# 02_RF_FRONT_END.net
KiCad netlist of a schematic drawn in Altium Designer
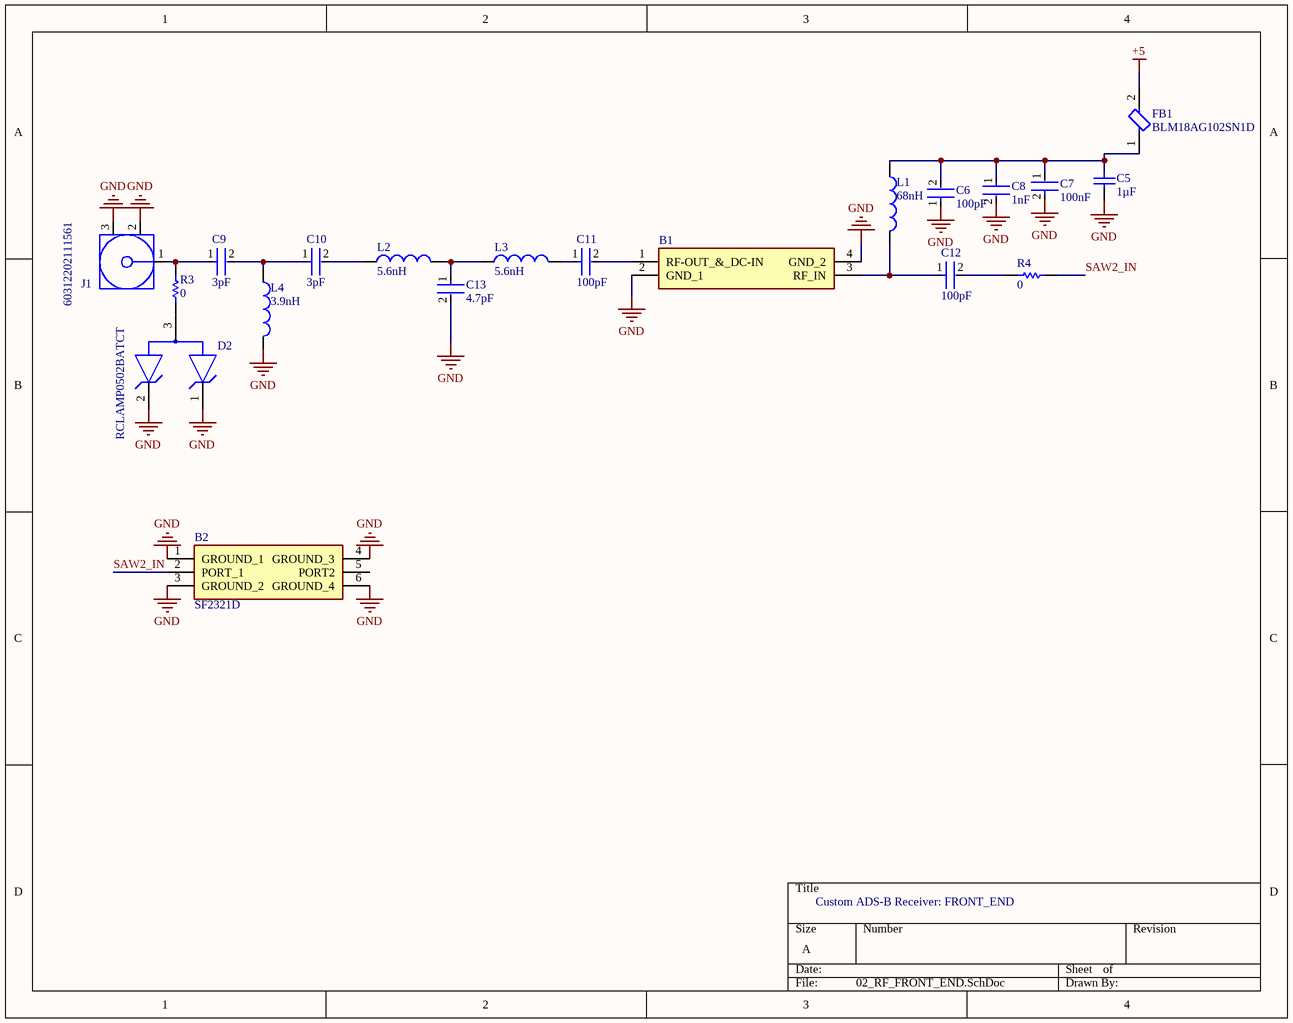
[diagram p0: 02_RF_FRONT_END.SchDoc]

(export (version "E")
  (design (tool "Eeschema 10.0.6"))
  (components
    (comp (ref "B1")
      (value "PSA4-5043+")
      (footprint "PSA45043")
      (libsource (lib "Maksym Pleshyvtsev") (part "PSA4-5043+"))
    )
    (comp (ref "B2")
      (value "SF2321D")
      (footprint "SF2321D")
      (description "Signal Conditioning 433.92MHZ")
      (fields (field (name "MOUSER PART NUMBER") "81-SF2321D"))
      (libsource (lib "Maksym Pleshyvtsev") (part "SF2321D"))
    )
    (comp (ref "C5")
      (value "1µF")
      (footprint "RESC1608X100N")
      (description "0603 1 uF 10 V ±10% Tolerance X5R SMT Multilayer Ceramic Capacitor")
      (fields (field (name "TOLERANCE") "10%") (field (name "Comment") "GRM188R61A105KA61D"))
      (libsource (lib "Maksym Pleshyvtsev") (part "CAP-NP-2"))
    )
    (comp (ref "C6")
      (value "100pF")
      (footprint "FP-GCM155-0_05-MFG")
      (description "50V 100pF C0G ±5% 0402 Multilayer Ceramic Capacitors MLCC - SMD/SMT ROHS")
      (fields (field (name "TOLERANCE") "5%") (field (name "Comment") "GCM1555C1H101JA16J"))
      (libsource (lib "Maksym Pleshyvtsev") (part "02cd4be3c70576c341d710602a673aa"))
    )
    (comp (ref "C7")
      (value "100nF")
      (footprint "FP-GRM15-MFG")
      (description "16V 100nF X7R ±10% 0402 Multilayer Ceramic Capacitors MLCC - SMD/SMT ROHS")
      (fields (field (name "TOLERANCE") "10%") (field (name "Comment") "GRM155R71C104KA88D"))
      (libsource (lib "Maksym Pleshyvtsev") (part "236180d848d6139a670b325ea6854c9"))
    )
    (comp (ref "C8")
      (value "1nF")
      (footprint "FP-GRM155-0_05-MFG")
      (description "50V 1nF C0G ±5% 0402 Multilayer Ceramic Capacitors MLCC - SMD/SMT ROHS")
      (fields (field (name "TOLERANCE") "5%") (field (name "Comment") "GRM1555C1H102JA01D"))
      (libsource (lib "Maksym Pleshyvtsev") (part "02cd4be3c70576c341d710602a673aa"))
    )
    (comp (ref "C9")
      (value "3pF")
      (footprint "FP-GJM155-0_05-IPC_A")
      (description "0402 3 pF 50V ±0.25 pF Tolerance C0G SMT Multilayer Ceramic Capacitor")
      (fields (field (name "Comment") "GJM1555C1H3R0CB01D"))
      (libsource (lib "Maksym Pleshyvtsev") (part "02cd4be3c70576c341d710602a673aa"))
    )
    (comp (ref "C10")
      (value "3pF")
      (footprint "FP-GJM155-0_05-IPC_A")
      (description "0402 3 pF 50V ±0.25 pF Tolerance C0G SMT Multilayer Ceramic Capacitor")
      (fields (field (name "Comment") "GJM1555C1H3R0CB01D"))
      (libsource (lib "Maksym Pleshyvtsev") (part "02cd4be3c70576c341d710602a673aa"))
    )
    (comp (ref "C11")
      (value "100pF")
      (footprint "FP-GCM155-0_05-MFG")
      (description "50V 100pF C0G ±5% 0402 Multilayer Ceramic Capacitors MLCC - SMD/SMT ROHS")
      (fields (field (name "TOLERANCE") "5%") (field (name "Comment") "GCM1555C1H101JA16J"))
      (libsource (lib "Maksym Pleshyvtsev") (part "02cd4be3c70576c341d710602a673aa"))
    )
    (comp (ref "C12")
      (value "100pF")
      (footprint "FP-GCM155-0_05-MFG")
      (description "50V 100pF C0G ±5% 0402 Multilayer Ceramic Capacitors MLCC - SMD/SMT ROHS")
      (fields (field (name "TOLERANCE") "5%") (field (name "Comment") "GCM1555C1H101JA16J"))
      (libsource (lib "Maksym Pleshyvtsev") (part "02cd4be3c70576c341d710602a673aa"))
    )
    (comp (ref "C13")
      (value "4.7pF")
      (footprint "FP-GJM155-0_05-MFG")
      (description "0402 4.7pF 50V ±0.25 pF Tolerance C0G SMT Multilayer Ceramic Capacitor")
      (fields (field (name "Comment") "GJM1555C1H4R7CB01D"))
      (libsource (lib "Maksym Pleshyvtsev") (part "02cd4be3c70576c341d710602a673aa"))
    )
    (comp (ref "D2")
      (value "RCLAMP0502BATCT")
      (footprint "FP-SC75-IPC_A")
      (description "ESD Suppressor Diode TVS Uni-Dir/Bi-Dir 5V 3-Pin SOT-523 T/R / TVS DIODE 5VWM 25VC SC75")
      (libsource (lib "Maksym Pleshyvtsev") (part "9603becf907846612ba46a8964e2875"))
    )
    (comp (ref "FB1")
      (value "BLM18AG102SN1D")
      (footprint "FP-BLM18-0_15-t0_8-MFG")
      (description "Ferrite Beads Multi-Layer 1KOhm 25% 100MHz 400mA 500mOhm DCR 0603 T/R")
      (libsource (lib "Maksym Pleshyvtsev") (part "5f30dd21d616792df468990f7003faa"))
    )
    (comp (ref "J1")
      (value "60312202111561")
      (footprint "60312202111561")
      (description "Rf Conn, Sma, Jack, 50 Ohm, End Launch Rohs Compliant: Yes")
      (libsource (lib "Maksym Pleshyvtsev") (part "Jack_2GND"))
    )
    (comp (ref "L1")
      (value "68nH")
      (footprint "INDC1811X102N")
      (description "RF inductor, ceramic core, 2% tol, SMT, RoHS, halogen-free")
      (fields (field (name "Comment") "Coilcraft 0603CS-68NX"))
      (libsource (lib "Maksym Pleshyvtsev") (part "IND-2"))
    )
    (comp (ref "L2")
      (value "5.6nH")
      (footprint "INDC1811X100N")
      (description "General Purpose Inductor, 0.0056uH, 5%, 1 Element, Ceramic-Core, SMD, 0603")
      (fields (field (name "TOLERANCE") "5%") (field (name "Comment") "0603CS5N6XJRW"))
      (libsource (lib "Maksym Pleshyvtsev") (part "IND-2"))
    )
    (comp (ref "L3")
      (value "5.6nH")
      (footprint "INDC1811X102N")
      (description "General Purpose Inductor, 0.0056uH, 5%, 1 Element, Ceramic-Core, SMD, 0603")
      (fields (field (name "TOLERANCE") "5%") (field (name "Comment") "0603CS5N6XJRW"))
      (libsource (lib "Maksym Pleshyvtsev") (part "IND-2"))
    )
    (comp (ref "L4")
      (value "3.9nH")
      (footprint "INDC1811X100N")
      (description "General Purpose Inductor, 0.0039uH, 5%, 1 Element, Ceramic-Core, SMD, 0603")
      (fields (field (name "TOLERANCE") "5%") (field (name "Comment") "0603CS-3N9XJRW"))
      (libsource (lib "Maksym Pleshyvtsev") (part "IND-2"))
    )
    (comp (ref "R3")
      (value "0")
      (footprint "RESC1608X55X25ML10T15")
      (description "Chip Resistor, 0 Ohm, 0.1 W, -55 to 155 degC, 0603 (1608 Metric)")
      (fields (field (name "POWER") "100mW") (field (name "TOLERANCE") "5%"))
      (libsource (lib "Maksym Pleshyvtsev") (part "RES-2"))
    )
    (comp (ref "R4")
      (value "0")
      (footprint "RESC1608X55X25ML10T15")
      (description "Chip Resistor, 0 Ohm, 0.1 W, -55 to 155 degC, 0603 (1608 Metric)")
      (fields (field (name "POWER") "100mW") (field (name "TOLERANCE") "5%"))
      (libsource (lib "Maksym Pleshyvtsev") (part "RES-2"))
    )
  )
  (nets
    (net (code "1") (name "+5") (class "Default")
      (node (ref "FB1") (pin "2") (pinfunction "2_2") (pintype "passive"))
    )
    (net (code "2") (name "/SAW2_IN") (class "Default")
      (node (ref "B2") (pin "2") (pinfunction "PORT_1_2") (pintype "passive"))
      (node (ref "R4") (pin "1") (pinfunction "1_1") (pintype "passive"))
    )
    (net (code "3") (name "GND") (class "Default")
      (node (ref "B1") (pin "2") (pinfunction "GND_1_2") (pintype "passive"))
      (node (ref "B1") (pin "4") (pinfunction "GND_2_4") (pintype "passive"))
      (node (ref "B2") (pin "1") (pinfunction "GROUND_1_1") (pintype "passive"))
      (node (ref "B2") (pin "3") (pinfunction "GROUND_2_3") (pintype "passive"))
      (node (ref "B2") (pin "4") (pinfunction "GROUND_3_4") (pintype "passive"))
      (node (ref "B2") (pin "6") (pinfunction "GROUND_4_6") (pintype "passive"))
      (node (ref "C13") (pin "2") (pinfunction "2_2") (pintype "passive"))
      (node (ref "C5") (pin "1") (pinfunction "1_1") (pintype "passive"))
      (node (ref "C6") (pin "1") (pinfunction "1_1") (pintype "passive"))
      (node (ref "C7") (pin "2") (pinfunction "2_2") (pintype "passive"))
      (node (ref "C8") (pin "2") (pinfunction "2_2") (pintype "passive"))
      (node (ref "D2") (pin "1") (pinfunction "1_CATHODE_1") (pintype "passive"))
      (node (ref "D2") (pin "2") (pinfunction "2_CATHODE_2") (pintype "passive"))
      (node (ref "J1") (pin "2") (pinfunction "GND_2") (pintype "passive"))
      (node (ref "J1") (pin "3") (pinfunction "GND_3") (pintype "passive"))
      (node (ref "L4") (pin "2") (pinfunction "2_2") (pintype "passive"))
    )
    (net (code "4") (name "Net-(B1-RF-OUT_&_DC-IN)") (class "Default")
      (node (ref "B1") (pin "1") (pinfunction "RF-OUT_&_DC-IN_1") (pintype "passive"))
      (node (ref "C11") (pin "2") (pinfunction "2_2") (pintype "passive"))
    )
    (net (code "5") (name "Net-(B1-RF_IN)") (class "Default")
      (node (ref "B1") (pin "3") (pinfunction "RF_IN_3") (pintype "passive"))
      (node (ref "C12") (pin "1") (pinfunction "1_1") (pintype "passive"))
      (node (ref "L1") (pin "2") (pinfunction "2_2") (pintype "passive"))
    )
    (net (code "6") (name "Net-(C5-Pad2)") (class "Default")
      (node (ref "C5") (pin "2") (pinfunction "2_2") (pintype "passive"))
      (node (ref "C6") (pin "2") (pinfunction "2_2") (pintype "passive"))
      (node (ref "C7") (pin "1") (pinfunction "1_1") (pintype "passive"))
      (node (ref "C8") (pin "1") (pinfunction "1_1") (pintype "passive"))
      (node (ref "FB1") (pin "1") (pinfunction "1_1") (pintype "passive"))
      (node (ref "L1") (pin "1") (pinfunction "1_1") (pintype "passive"))
    )
    (net (code "7") (name "Net-(C10-Pad1)") (class "Default")
      (node (ref "C10") (pin "1") (pinfunction "1_1") (pintype "passive"))
      (node (ref "C9") (pin "2") (pinfunction "2_2") (pintype "passive"))
      (node (ref "L4") (pin "1") (pinfunction "1_1") (pintype "passive"))
    )
    (net (code "8") (name "Net-(C10-Pad2)") (class "Default")
      (node (ref "C10") (pin "2") (pinfunction "2_2") (pintype "passive"))
      (node (ref "L2") (pin "1") (pinfunction "1_1") (pintype "passive"))
    )
    (net (code "9") (name "Net-(C11-Pad1)") (class "Default")
      (node (ref "C11") (pin "1") (pinfunction "1_1") (pintype "passive"))
      (node (ref "L3") (pin "2") (pinfunction "2_2") (pintype "passive"))
    )
    (net (code "10") (name "Net-(C12-Pad2)") (class "Default")
      (node (ref "C12") (pin "2") (pinfunction "2_2") (pintype "passive"))
      (node (ref "R4") (pin "2") (pinfunction "2_2") (pintype "passive"))
    )
    (net (code "11") (name "Net-(C13-Pad1)") (class "Default")
      (node (ref "C13") (pin "1") (pinfunction "1_1") (pintype "passive"))
      (node (ref "L2") (pin "2") (pinfunction "2_2") (pintype "passive"))
      (node (ref "L3") (pin "1") (pinfunction "1_1") (pintype "passive"))
    )
    (net (code "12") (name "Net-(D2-COMMON_ANODE)") (class "Default")
      (node (ref "D2") (pin "3") (pinfunction "COMMON_ANODE_3") (pintype "passive"))
      (node (ref "R3") (pin "1") (pinfunction "1_1") (pintype "passive"))
    )
    (net (code "13") (name "Net-(J1-Signal)") (class "Default")
      (node (ref "C9") (pin "1") (pinfunction "1_1") (pintype "passive"))
      (node (ref "J1") (pin "1") (pinfunction "Signal_1") (pintype "passive"))
      (node (ref "R3") (pin "2") (pinfunction "2_2") (pintype "passive"))
    )
    (net (code "14") (name "unconnected-(B2-PORT2-Pad5)") (class "Default")
      (node (ref "B2") (pin "5") (pinfunction "PORT2_5") (pintype "passive"))
    )
  )
)
